# 2_DDR4_16bits.net
KiCad netlist of a schematic drawn in Altium Designer
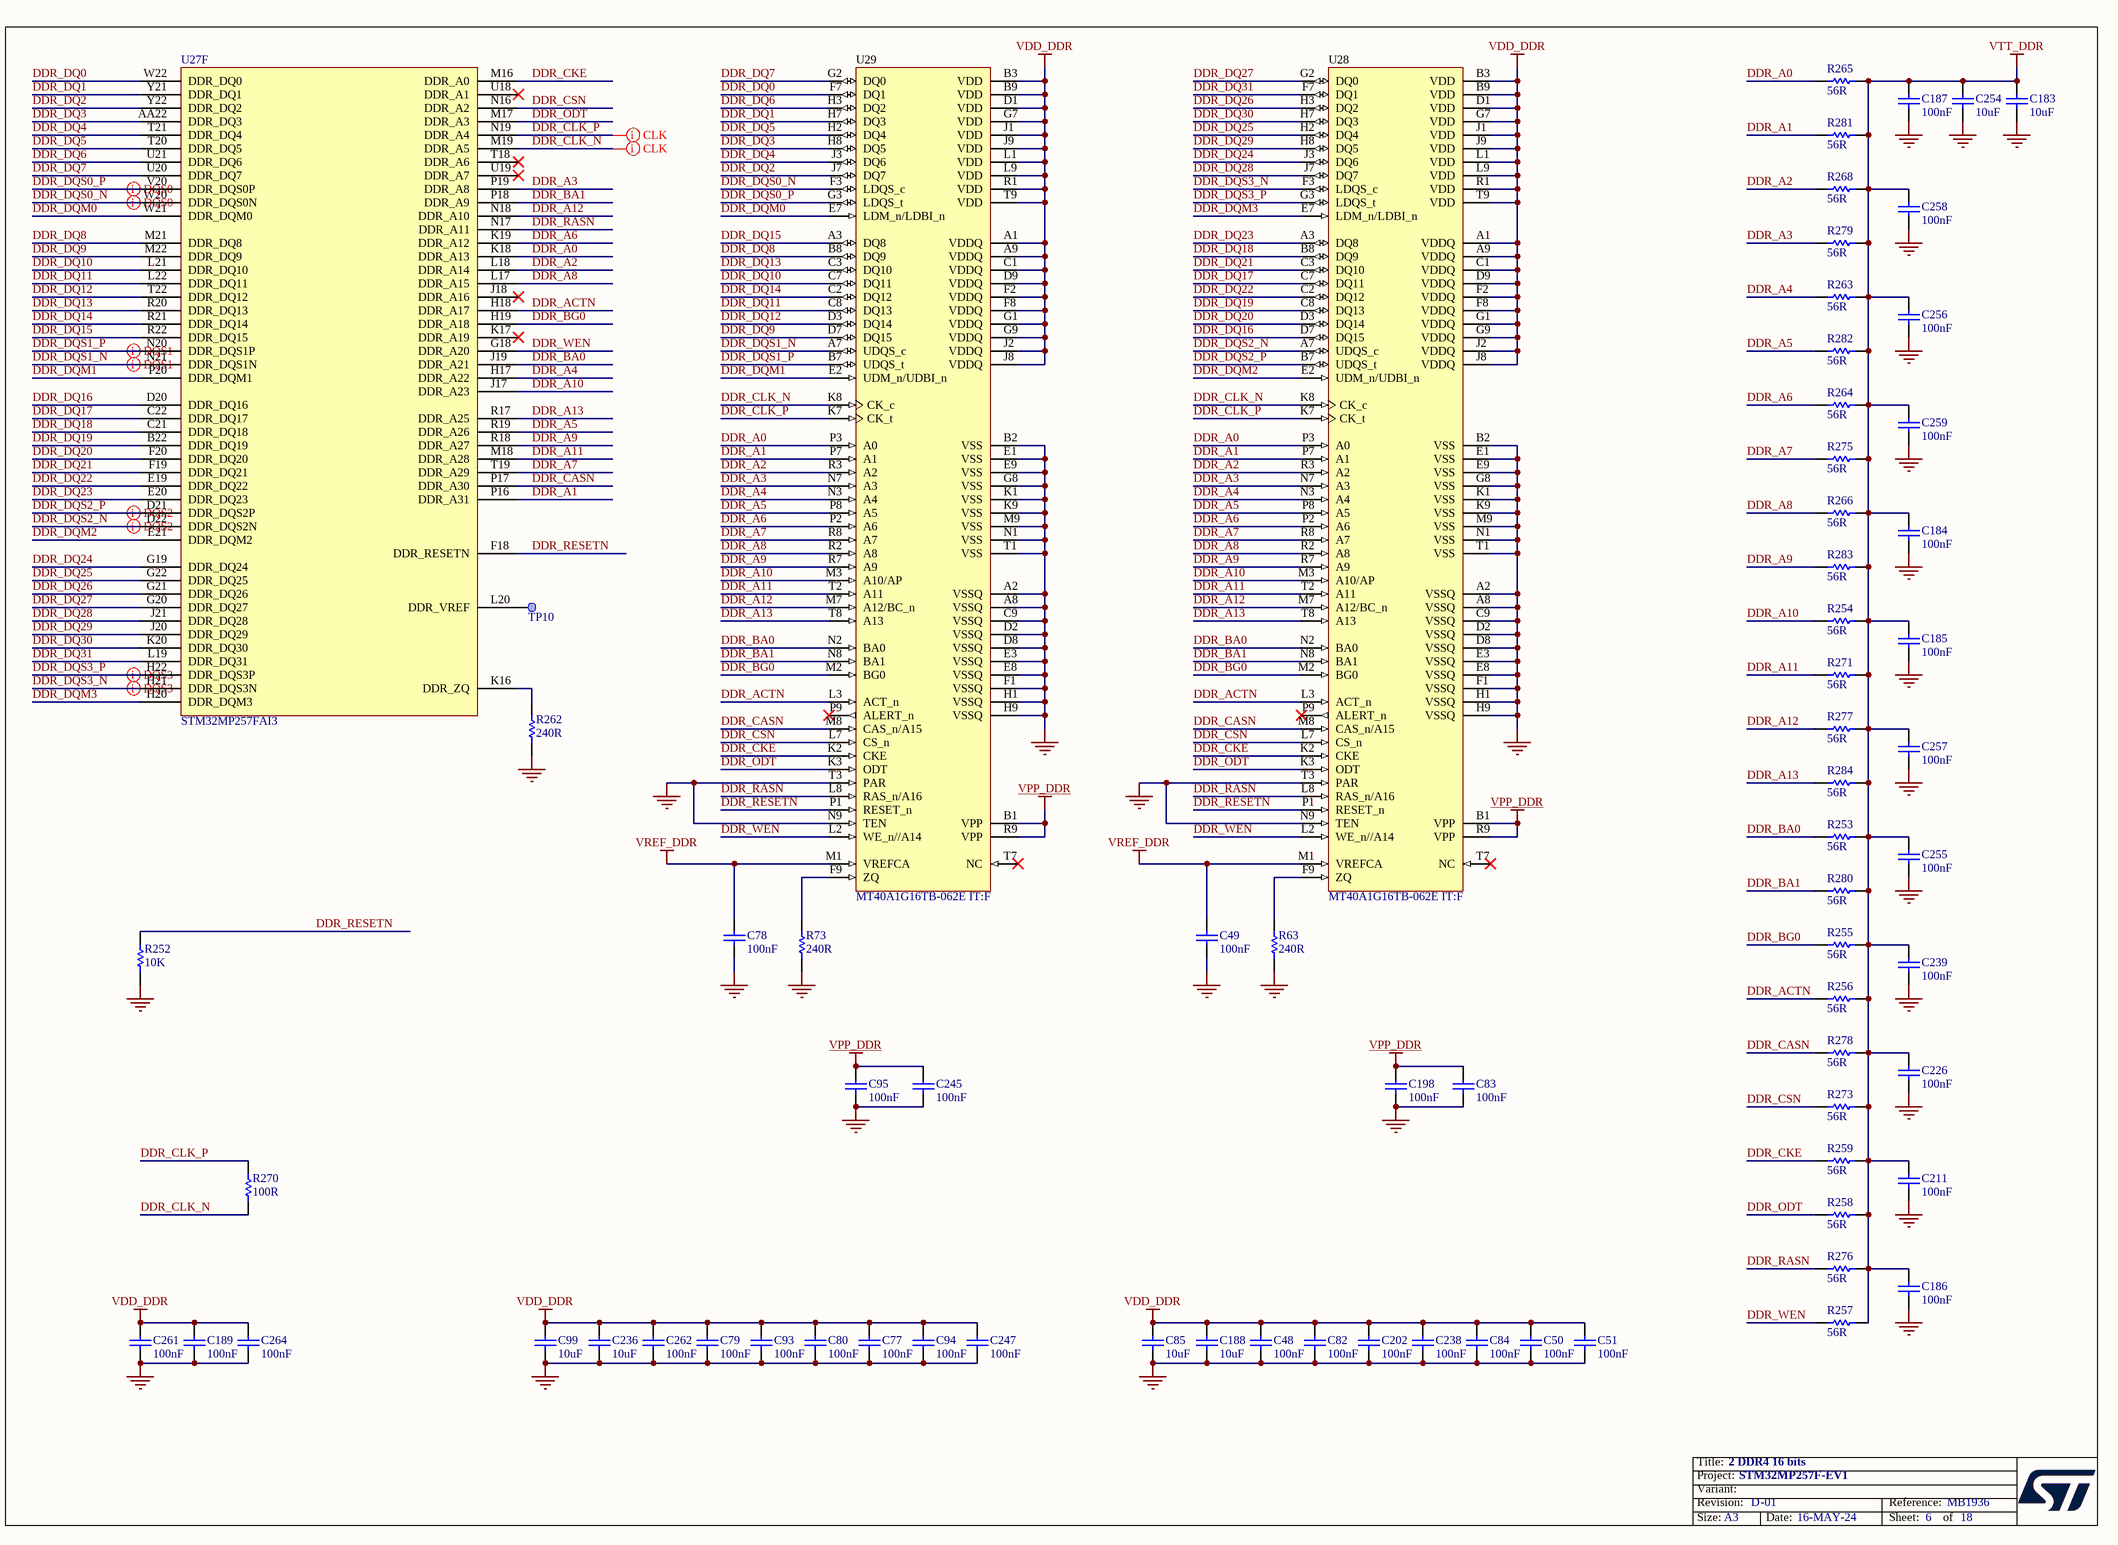
[diagram p0: 2_DDR4_16bits.SchDoc]

(export (version "E")
  (design (tool "Eeschema 10.0.6"))
  (components
    (comp (ref "C48")
      (value "100nF")
      (footprint "MCD_PARTS:C0402")
      (description "Capacitor, MLCC, 100nF, 16V, X7R, +/-10%, 0402, T=0.5mm")
      (fields (field (name "INTERNAL_PART_NUMBER") "MCD-00006") (field (name "MANUFACTURER") "YAGEO"))
      (libsource (lib "MCD_PARTS_database") (part "Capacitor"))
    )
    (comp (ref "C49")
      (value "100nF")
      (footprint "MCD_PARTS:C0402")
      (description "Capacitor, MLCC, 100nF, 16V, X7R, +/-10%, 0402, T=0.5mm")
      (fields (field (name "INTERNAL_PART_NUMBER") "MCD-00006") (field (name "MANUFACTURER") "YAGEO"))
      (libsource (lib "MCD_PARTS_database") (part "Capacitor"))
    )
    (comp (ref "C50")
      (value "100nF")
      (footprint "MCD_PARTS:C0402")
      (description "Capacitor, MLCC, 100nF, 16V, X7R, +/-10%, 0402, T=0.5mm")
      (fields (field (name "INTERNAL_PART_NUMBER") "MCD-00006") (field (name "MANUFACTURER") "YAGEO"))
      (libsource (lib "MCD_PARTS_database") (part "Capacitor"))
    )
    (comp (ref "C51")
      (value "100nF")
      (footprint "MCD_PARTS:C0402")
      (description "Capacitor, MLCC, 100nF, 16V, X7R, +/-10%, 0402, T=0.5mm")
      (fields (field (name "INTERNAL_PART_NUMBER") "MCD-00006") (field (name "MANUFACTURER") "YAGEO"))
      (libsource (lib "MCD_PARTS_database") (part "Capacitor"))
    )
    (comp (ref "C77")
      (value "100nF")
      (footprint "MCD_PARTS:C0402")
      (description "Capacitor, MLCC, 100nF, 16V, X7R, +/-10%, 0402, T=0.5mm")
      (fields (field (name "INTERNAL_PART_NUMBER") "MCD-00006") (field (name "MANUFACTURER") "YAGEO"))
      (libsource (lib "MCD_PARTS_database") (part "Capacitor"))
    )
    (comp (ref "C78")
      (value "100nF")
      (footprint "MCD_PARTS:C0402")
      (description "Capacitor, MLCC, 100nF, 16V, X7R, +/-10%, 0402, T=0.5mm")
      (fields (field (name "INTERNAL_PART_NUMBER") "MCD-00006") (field (name "MANUFACTURER") "YAGEO"))
      (libsource (lib "MCD_PARTS_database") (part "Capacitor"))
    )
    (comp (ref "C79")
      (value "100nF")
      (footprint "MCD_PARTS:C0402")
      (description "Capacitor, MLCC, 100nF, 16V, X7R, +/-10%, 0402, T=0.5mm")
      (fields (field (name "INTERNAL_PART_NUMBER") "MCD-00006") (field (name "MANUFACTURER") "YAGEO"))
      (libsource (lib "MCD_PARTS_database") (part "Capacitor"))
    )
    (comp (ref "C80")
      (value "100nF")
      (footprint "MCD_PARTS:C0402")
      (description "Capacitor, MLCC, 100nF, 16V, X7R, +/-10%, 0402, T=0.5mm")
      (fields (field (name "INTERNAL_PART_NUMBER") "MCD-00006") (field (name "MANUFACTURER") "YAGEO"))
      (libsource (lib "MCD_PARTS_database") (part "Capacitor"))
    )
    (comp (ref "C82")
      (value "100nF")
      (footprint "MCD_PARTS:C0402")
      (description "Capacitor, MLCC, 100nF, 16V, X7R, +/-10%, 0402, T=0.5mm")
      (fields (field (name "INTERNAL_PART_NUMBER") "MCD-00006") (field (name "MANUFACTURER") "YAGEO"))
      (libsource (lib "MCD_PARTS_database") (part "Capacitor"))
    )
    (comp (ref "C83")
      (value "100nF")
      (footprint "MCD_PARTS:C0402")
      (description "Capacitor, MLCC, 100nF, 16V, X7R, +/-10%, 0402, T=0.5mm")
      (fields (field (name "INTERNAL_PART_NUMBER") "MCD-00006") (field (name "MANUFACTURER") "YAGEO"))
      (libsource (lib "MCD_PARTS_database") (part "Capacitor"))
    )
    (comp (ref "C84")
      (value "100nF")
      (footprint "MCD_PARTS:C0402")
      (description "Capacitor, MLCC, 100nF, 16V, X7R, +/-10%, 0402, T=0.5mm")
      (fields (field (name "INTERNAL_PART_NUMBER") "MCD-00006") (field (name "MANUFACTURER") "YAGEO"))
      (libsource (lib "MCD_PARTS_database") (part "Capacitor"))
    )
    (comp (ref "C85")
      (value "10uF")
      (footprint "MCD_PARTS:C0603")
      (description "Capacitor, MLCC, 10uF, 6V3, X5R, +/-20%, 0603, T=0,8mm")
      (fields (field (name "INTERNAL_PART_NUMBER") "MCD-01341") (field (name "MANUFACTURER") "MURATA"))
      (libsource (lib "MCD_PARTS_database") (part "Capacitor"))
    )
    (comp (ref "C93")
      (value "100nF")
      (footprint "MCD_PARTS:C0402")
      (description "Capacitor, MLCC, 100nF, 16V, X7R, +/-10%, 0402, T=0.5mm")
      (fields (field (name "INTERNAL_PART_NUMBER") "MCD-00006") (field (name "MANUFACTURER") "YAGEO"))
      (libsource (lib "MCD_PARTS_database") (part "Capacitor"))
    )
    (comp (ref "C94")
      (value "100nF")
      (footprint "MCD_PARTS:C0402")
      (description "Capacitor, MLCC, 100nF, 16V, X7R, +/-10%, 0402, T=0.5mm")
      (fields (field (name "INTERNAL_PART_NUMBER") "MCD-00006") (field (name "MANUFACTURER") "YAGEO"))
      (libsource (lib "MCD_PARTS_database") (part "Capacitor"))
    )
    (comp (ref "C95")
      (value "100nF")
      (footprint "MCD_PARTS:C0402")
      (description "Capacitor, MLCC, 100nF, 16V, X7R, +/-10%, 0402, T=0.5mm")
      (fields (field (name "INTERNAL_PART_NUMBER") "MCD-00006") (field (name "MANUFACTURER") "YAGEO"))
      (libsource (lib "MCD_PARTS_database") (part "Capacitor"))
    )
    (comp (ref "C99")
      (value "10uF")
      (footprint "MCD_PARTS:C0603")
      (description "Capacitor, MLCC, 10uF, 6V3, X5R, +/-20%, 0603, T=0,8mm")
      (fields (field (name "INTERNAL_PART_NUMBER") "MCD-01341") (field (name "MANUFACTURER") "MURATA"))
      (libsource (lib "MCD_PARTS_database") (part "Capacitor"))
    )
    (comp (ref "C183")
      (value "10uF")
      (footprint "C0603")
      (description "Capacitor, MLCC, 10uF, 10V, X5R, +/-10%, 0603, T=0.8mm")
      (fields (field (name "INTERNAL_PART_NUMBER") "MCD-00099") (field (name "MANUFACTURER") "MURATA"))
      (libsource (lib "MCD_PARTS_database") (part "Capacitor"))
    )
    (comp (ref "C184")
      (value "100nF")
      (footprint "MCD_PARTS:C0402")
      (description "Capacitor, MLCC, 100nF, 16V, X7R, +/-10%, 0402, T=0.5mm")
      (fields (field (name "INTERNAL_PART_NUMBER") "MCD-00006") (field (name "MANUFACTURER") "YAGEO"))
      (libsource (lib "MCD_PARTS_database") (part "Capacitor"))
    )
    (comp (ref "C185")
      (value "100nF")
      (footprint "MCD_PARTS:C0402")
      (description "Capacitor, MLCC, 100nF, 16V, X7R, +/-10%, 0402, T=0.5mm")
      (fields (field (name "INTERNAL_PART_NUMBER") "MCD-00006") (field (name "MANUFACTURER") "YAGEO"))
      (libsource (lib "MCD_PARTS_database") (part "Capacitor"))
    )
    (comp (ref "C186")
      (value "100nF")
      (footprint "MCD_PARTS:C0402")
      (description "Capacitor, MLCC, 100nF, 16V, X7R, +/-10%, 0402, T=0.5mm")
      (fields (field (name "INTERNAL_PART_NUMBER") "MCD-00006") (field (name "MANUFACTURER") "YAGEO"))
      (libsource (lib "MCD_PARTS_database") (part "Capacitor"))
    )
    (comp (ref "C187")
      (value "100nF")
      (footprint "MCD_PARTS:C0402")
      (description "Capacitor, MLCC, 100nF, 16V, X7R, +/-10%, 0402, T=0.5mm")
      (fields (field (name "INTERNAL_PART_NUMBER") "MCD-00006") (field (name "MANUFACTURER") "YAGEO"))
      (libsource (lib "MCD_PARTS_database") (part "Capacitor"))
    )
    (comp (ref "C188")
      (value "10uF")
      (footprint "MCD_PARTS:C0603")
      (description "Capacitor, MLCC, 10uF, 6V3, X5R, +/-20%, 0603, T=0,8mm")
      (fields (field (name "INTERNAL_PART_NUMBER") "MCD-01341") (field (name "MANUFACTURER") "MURATA"))
      (libsource (lib "MCD_PARTS_database") (part "Capacitor"))
    )
    (comp (ref "C189")
      (value "100nF")
      (footprint "MCD_PARTS:C0402")
      (description "Capacitor, MLCC, 100nF, 16V, X7R, +/-10%, 0402, T=0.5mm")
      (fields (field (name "INTERNAL_PART_NUMBER") "MCD-00006") (field (name "MANUFACTURER") "YAGEO"))
      (libsource (lib "MCD_PARTS_database") (part "Capacitor"))
    )
    (comp (ref "C198")
      (value "100nF")
      (footprint "MCD_PARTS:C0402")
      (description "Capacitor, MLCC, 100nF, 16V, X7R, +/-10%, 0402, T=0.5mm")
      (fields (field (name "INTERNAL_PART_NUMBER") "MCD-00006") (field (name "MANUFACTURER") "YAGEO"))
      (libsource (lib "MCD_PARTS_database") (part "Capacitor"))
    )
    (comp (ref "C202")
      (value "100nF")
      (footprint "MCD_PARTS:C0402")
      (description "Capacitor, MLCC, 100nF, 16V, X7R, +/-10%, 0402, T=0.5mm")
      (fields (field (name "INTERNAL_PART_NUMBER") "MCD-00006") (field (name "MANUFACTURER") "YAGEO"))
      (libsource (lib "MCD_PARTS_database") (part "Capacitor"))
    )
    (comp (ref "C211")
      (value "100nF")
      (footprint "MCD_PARTS:C0402")
      (description "Capacitor, MLCC, 100nF, 16V, X7R, +/-10%, 0402, T=0.5mm")
      (fields (field (name "INTERNAL_PART_NUMBER") "MCD-00006") (field (name "MANUFACTURER") "YAGEO"))
      (libsource (lib "MCD_PARTS_database") (part "Capacitor"))
    )
    (comp (ref "C226")
      (value "100nF")
      (footprint "MCD_PARTS:C0402")
      (description "Capacitor, MLCC, 100nF, 16V, X7R, +/-10%, 0402, T=0.5mm")
      (fields (field (name "INTERNAL_PART_NUMBER") "MCD-00006") (field (name "MANUFACTURER") "YAGEO"))
      (libsource (lib "MCD_PARTS_database") (part "Capacitor"))
    )
    (comp (ref "C236")
      (value "10uF")
      (footprint "MCD_PARTS:C0603")
      (description "Capacitor, MLCC, 10uF, 6V3, X5R, +/-20%, 0603, T=0,8mm")
      (fields (field (name "INTERNAL_PART_NUMBER") "MCD-01341") (field (name "MANUFACTURER") "MURATA"))
      (libsource (lib "MCD_PARTS_database") (part "Capacitor"))
    )
    (comp (ref "C238")
      (value "100nF")
      (footprint "MCD_PARTS:C0402")
      (description "Capacitor, MLCC, 100nF, 16V, X7R, +/-10%, 0402, T=0.5mm")
      (fields (field (name "INTERNAL_PART_NUMBER") "MCD-00006") (field (name "MANUFACTURER") "YAGEO"))
      (libsource (lib "MCD_PARTS_database") (part "Capacitor"))
    )
    (comp (ref "C239")
      (value "100nF")
      (footprint "MCD_PARTS:C0402")
      (description "Capacitor, MLCC, 100nF, 16V, X7R, +/-10%, 0402, T=0.5mm")
      (fields (field (name "INTERNAL_PART_NUMBER") "MCD-00006") (field (name "MANUFACTURER") "YAGEO"))
      (libsource (lib "MCD_PARTS_database") (part "Capacitor"))
    )
    (comp (ref "C245")
      (value "100nF")
      (footprint "MCD_PARTS:C0402")
      (description "Capacitor, MLCC, 100nF, 16V, X7R, +/-10%, 0402, T=0.5mm")
      (fields (field (name "INTERNAL_PART_NUMBER") "MCD-00006") (field (name "MANUFACTURER") "YAGEO"))
      (libsource (lib "MCD_PARTS_database") (part "Capacitor"))
    )
    (comp (ref "C247")
      (value "100nF")
      (footprint "MCD_PARTS:C0402")
      (description "Capacitor, MLCC, 100nF, 16V, X7R, +/-10%, 0402, T=0.5mm")
      (fields (field (name "INTERNAL_PART_NUMBER") "MCD-00006") (field (name "MANUFACTURER") "YAGEO"))
      (libsource (lib "MCD_PARTS_database") (part "Capacitor"))
    )
    (comp (ref "C254")
      (value "10uF")
      (footprint "C0603")
      (description "Capacitor, MLCC, 10uF, 10V, X5R, +/-10%, 0603, T=0.8mm")
      (fields (field (name "INTERNAL_PART_NUMBER") "MCD-00099") (field (name "MANUFACTURER") "MURATA"))
      (libsource (lib "MCD_PARTS_database") (part "Capacitor"))
    )
    (comp (ref "C255")
      (value "100nF")
      (footprint "MCD_PARTS:C0402")
      (description "Capacitor, MLCC, 100nF, 16V, X7R, +/-10%, 0402, T=0.5mm")
      (fields (field (name "INTERNAL_PART_NUMBER") "MCD-00006") (field (name "MANUFACTURER") "YAGEO"))
      (libsource (lib "MCD_PARTS_database") (part "Capacitor"))
    )
    (comp (ref "C256")
      (value "100nF")
      (footprint "MCD_PARTS:C0402")
      (description "Capacitor, MLCC, 100nF, 16V, X7R, +/-10%, 0402, T=0.5mm")
      (fields (field (name "INTERNAL_PART_NUMBER") "MCD-00006") (field (name "MANUFACTURER") "YAGEO"))
      (libsource (lib "MCD_PARTS_database") (part "Capacitor"))
    )
    (comp (ref "C257")
      (value "100nF")
      (footprint "MCD_PARTS:C0402")
      (description "Capacitor, MLCC, 100nF, 16V, X7R, +/-10%, 0402, T=0.5mm")
      (fields (field (name "INTERNAL_PART_NUMBER") "MCD-00006") (field (name "MANUFACTURER") "YAGEO"))
      (libsource (lib "MCD_PARTS_database") (part "Capacitor"))
    )
    (comp (ref "C258")
      (value "100nF")
      (footprint "MCD_PARTS:C0402")
      (description "Capacitor, MLCC, 100nF, 16V, X7R, +/-10%, 0402, T=0.5mm")
      (fields (field (name "INTERNAL_PART_NUMBER") "MCD-00006") (field (name "MANUFACTURER") "YAGEO"))
      (libsource (lib "MCD_PARTS_database") (part "Capacitor"))
    )
    (comp (ref "C259")
      (value "100nF")
      (footprint "MCD_PARTS:C0402")
      (description "Capacitor, MLCC, 100nF, 16V, X7R, +/-10%, 0402, T=0.5mm")
      (fields (field (name "INTERNAL_PART_NUMBER") "MCD-00006") (field (name "MANUFACTURER") "YAGEO"))
      (libsource (lib "MCD_PARTS_database") (part "Capacitor"))
    )
    (comp (ref "C261")
      (value "100nF")
      (footprint "MCD_PARTS:C0402")
      (description "Capacitor, MLCC, 100nF, 16V, X7R, +/-10%, 0402, T=0.5mm")
      (fields (field (name "INTERNAL_PART_NUMBER") "MCD-00006") (field (name "MANUFACTURER") "YAGEO"))
      (libsource (lib "MCD_PARTS_database") (part "Capacitor"))
    )
    (comp (ref "C262")
      (value "100nF")
      (footprint "MCD_PARTS:C0402")
      (description "Capacitor, MLCC, 100nF, 16V, X7R, +/-10%, 0402, T=0.5mm")
      (fields (field (name "INTERNAL_PART_NUMBER") "MCD-00006") (field (name "MANUFACTURER") "YAGEO"))
      (libsource (lib "MCD_PARTS_database") (part "Capacitor"))
    )
    (comp (ref "C264")
      (value "100nF")
      (footprint "MCD_PARTS:C0402")
      (description "Capacitor, MLCC, 100nF, 16V, X7R, +/-10%, 0402, T=0.5mm")
      (fields (field (name "INTERNAL_PART_NUMBER") "MCD-00006") (field (name "MANUFACTURER") "YAGEO"))
      (libsource (lib "MCD_PARTS_database") (part "Capacitor"))
    )
    (comp (ref "R63")
      (value "240R")
      (footprint "MCD_PARTS:R0201_H0P23")
      (description "Resistor,240R,0201,1%,1/20W")
      (fields (field (name "INTERNAL_PART_NUMBER") "MCD-02253") (field (name "MANUFACTURER") "YAGEO"))
      (libsource (lib "MCD_PARTS_database") (part "Resistor"))
    )
    (comp (ref "R73")
      (value "240R")
      (footprint "MCD_PARTS:R0201_H0P23")
      (description "Resistor,240R,0201,1%,1/20W")
      (fields (field (name "INTERNAL_PART_NUMBER") "MCD-02253") (field (name "MANUFACTURER") "YAGEO"))
      (libsource (lib "MCD_PARTS_database") (part "Resistor"))
    )
    (comp (ref "R252")
      (value "10K")
      (footprint "MCD_PARTS:R0402")
      (description "Resistor,10K,0402,1%,1/16W")
      (fields (field (name "INTERNAL_PART_NUMBER") "MCD-00053") (field (name "BMS_PART_NUMBER") "9131590"))
      (libsource (lib "MCD_PARTS_database") (part "Resistor"))
    )
    (comp (ref "R253")
      (value "56R")
      (footprint "MCD_PARTS:R0402")
      (description "Resistor, 56R, 0402, +/-1%, 1/16W")
      (fields (field (name "INTERNAL_PART_NUMBER") "MCD-00054") (field (name "MANUFACTURER") "YAGEO"))
      (libsource (lib "MCD_PARTS_database") (part "Resistor"))
    )
    (comp (ref "R254")
      (value "56R")
      (footprint "MCD_PARTS:R0402")
      (description "Resistor, 56R, 0402, +/-1%, 1/16W")
      (fields (field (name "INTERNAL_PART_NUMBER") "MCD-00054") (field (name "MANUFACTURER") "YAGEO"))
      (libsource (lib "MCD_PARTS_database") (part "Resistor"))
    )
    (comp (ref "R255")
      (value "56R")
      (footprint "MCD_PARTS:R0402")
      (description "Resistor, 56R, 0402, +/-1%, 1/16W")
      (fields (field (name "INTERNAL_PART_NUMBER") "MCD-00054") (field (name "MANUFACTURER") "YAGEO"))
      (libsource (lib "MCD_PARTS_database") (part "Resistor"))
    )
    (comp (ref "R256")
      (value "56R")
      (footprint "MCD_PARTS:R0402")
      (description "Resistor, 56R, 0402, +/-1%, 1/16W")
      (fields (field (name "INTERNAL_PART_NUMBER") "MCD-00054") (field (name "MANUFACTURER") "YAGEO"))
      (libsource (lib "MCD_PARTS_database") (part "Resistor"))
    )
    (comp (ref "R257")
      (value "56R")
      (footprint "MCD_PARTS:R0402")
      (description "Resistor, 56R, 0402, +/-1%, 1/16W")
      (fields (field (name "INTERNAL_PART_NUMBER") "MCD-00054") (field (name "MANUFACTURER") "YAGEO"))
      (libsource (lib "MCD_PARTS_database") (part "Resistor"))
    )
    (comp (ref "R258")
      (value "56R")
      (footprint "MCD_PARTS:R0402")
      (description "Resistor, 56R, 0402, +/-1%, 1/16W")
      (fields (field (name "INTERNAL_PART_NUMBER") "MCD-00054") (field (name "MANUFACTURER") "YAGEO"))
      (libsource (lib "MCD_PARTS_database") (part "Resistor"))
    )
    (comp (ref "R259")
      (value "56R")
      (footprint "MCD_PARTS:R0402")
      (description "Resistor, 56R, 0402, +/-1%, 1/16W")
      (fields (field (name "INTERNAL_PART_NUMBER") "MCD-00054") (field (name "MANUFACTURER") "YAGEO"))
      (libsource (lib "MCD_PARTS_database") (part "Resistor"))
    )
    (comp (ref "R262")
      (value "240R")
      (footprint "MCD_PARTS:R0201_H0P23")
      (description "Resistor,240R,0201,1%,1/20W")
      (fields (field (name "INTERNAL_PART_NUMBER") "MCD-02253") (field (name "MANUFACTURER") "YAGEO"))
      (libsource (lib "MCD_PARTS_database") (part "Resistor"))
    )
    (comp (ref "R263")
      (value "56R")
      (footprint "MCD_PARTS:R0402")
      (description "Resistor, 56R, 0402, +/-1%, 1/16W")
      (fields (field (name "INTERNAL_PART_NUMBER") "MCD-00054") (field (name "MANUFACTURER") "YAGEO"))
      (libsource (lib "MCD_PARTS_database") (part "Resistor"))
    )
    (comp (ref "R264")
      (value "56R")
      (footprint "MCD_PARTS:R0402")
      (description "Resistor, 56R, 0402, +/-1%, 1/16W")
      (fields (field (name "INTERNAL_PART_NUMBER") "MCD-00054") (field (name "MANUFACTURER") "YAGEO"))
      (libsource (lib "MCD_PARTS_database") (part "Resistor"))
    )
    (comp (ref "R265")
      (value "56R")
      (footprint "MCD_PARTS:R0402")
      (description "Resistor, 56R, 0402, +/-1%, 1/16W")
      (fields (field (name "INTERNAL_PART_NUMBER") "MCD-00054") (field (name "MANUFACTURER") "YAGEO"))
      (libsource (lib "MCD_PARTS_database") (part "Resistor"))
    )
    (comp (ref "R266")
      (value "56R")
      (footprint "MCD_PARTS:R0402")
      (description "Resistor, 56R, 0402, +/-1%, 1/16W")
      (fields (field (name "INTERNAL_PART_NUMBER") "MCD-00054") (field (name "MANUFACTURER") "YAGEO"))
      (libsource (lib "MCD_PARTS_database") (part "Resistor"))
    )
    (comp (ref "R268")
      (value "56R")
      (footprint "MCD_PARTS:R0402")
      (description "Resistor, 56R, 0402, +/-1%, 1/16W")
      (fields (field (name "INTERNAL_PART_NUMBER") "MCD-00054") (field (name "MANUFACTURER") "YAGEO"))
      (libsource (lib "MCD_PARTS_database") (part "Resistor"))
    )
    (comp (ref "R270")
      (value "100R")
      (footprint "MCD_PARTS:R0402")
      (description "Resistor,100R,0402,0,5%,1/16W,±100ppm/°C")
      (fields (field (name "INTERNAL_PART_NUMBER") "MCD-01819") (field (name "MANUFACTURER") "YAGEO"))
      (libsource (lib "MCD_PARTS_database") (part "Resistor"))
    )
    (comp (ref "R271")
      (value "56R")
      (footprint "MCD_PARTS:R0402")
      (description "Resistor, 56R, 0402, +/-1%, 1/16W")
      (fields (field (name "INTERNAL_PART_NUMBER") "MCD-00054") (field (name "MANUFACTURER") "YAGEO"))
      (libsource (lib "MCD_PARTS_database") (part "Resistor"))
    )
    (comp (ref "R273")
      (value "56R")
      (footprint "MCD_PARTS:R0402")
      (description "Resistor, 56R, 0402, +/-1%, 1/16W")
      (fields (field (name "INTERNAL_PART_NUMBER") "MCD-00054") (field (name "MANUFACTURER") "YAGEO"))
      (libsource (lib "MCD_PARTS_database") (part "Resistor"))
    )
    (comp (ref "R275")
      (value "56R")
      (footprint "MCD_PARTS:R0402")
      (description "Resistor, 56R, 0402, +/-1%, 1/16W")
      (fields (field (name "INTERNAL_PART_NUMBER") "MCD-00054") (field (name "MANUFACTURER") "YAGEO"))
      (libsource (lib "MCD_PARTS_database") (part "Resistor"))
    )
    (comp (ref "R276")
      (value "56R")
      (footprint "MCD_PARTS:R0402")
      (description "Resistor, 56R, 0402, +/-1%, 1/16W")
      (fields (field (name "INTERNAL_PART_NUMBER") "MCD-00054") (field (name "MANUFACTURER") "YAGEO"))
      (libsource (lib "MCD_PARTS_database") (part "Resistor"))
    )
    (comp (ref "R277")
      (value "56R")
      (footprint "MCD_PARTS:R0402")
      (description "Resistor, 56R, 0402, +/-1%, 1/16W")
      (fields (field (name "INTERNAL_PART_NUMBER") "MCD-00054") (field (name "MANUFACTURER") "YAGEO"))
      (libsource (lib "MCD_PARTS_database") (part "Resistor"))
    )
    (comp (ref "R278")
      (value "56R")
      (footprint "MCD_PARTS:R0402")
      (description "Resistor, 56R, 0402, +/-1%, 1/16W")
      (fields (field (name "INTERNAL_PART_NUMBER") "MCD-00054") (field (name "MANUFACTURER") "YAGEO"))
      (libsource (lib "MCD_PARTS_database") (part "Resistor"))
    )
    (comp (ref "R279")
      (value "56R")
      (footprint "MCD_PARTS:R0402")
      (description "Resistor, 56R, 0402, +/-1%, 1/16W")
      (fields (field (name "INTERNAL_PART_NUMBER") "MCD-00054") (field (name "MANUFACTURER") "YAGEO"))
      (libsource (lib "MCD_PARTS_database") (part "Resistor"))
    )
    (comp (ref "R280")
      (value "56R")
      (footprint "MCD_PARTS:R0402")
      (description "Resistor, 56R, 0402, +/-1%, 1/16W")
      (fields (field (name "INTERNAL_PART_NUMBER") "MCD-00054") (field (name "MANUFACTURER") "YAGEO"))
      (libsource (lib "MCD_PARTS_database") (part "Resistor"))
    )
    (comp (ref "R281")
      (value "56R")
      (footprint "MCD_PARTS:R0402")
      (description "Resistor, 56R, 0402, +/-1%, 1/16W")
      (fields (field (name "INTERNAL_PART_NUMBER") "MCD-00054") (field (name "MANUFACTURER") "YAGEO"))
      (libsource (lib "MCD_PARTS_database") (part "Resistor"))
    )
    (comp (ref "R282")
      (value "56R")
      (footprint "MCD_PARTS:R0402")
      (description "Resistor, 56R, 0402, +/-1%, 1/16W")
      (fields (field (name "INTERNAL_PART_NUMBER") "MCD-00054") (field (name "MANUFACTURER") "YAGEO"))
      (libsource (lib "MCD_PARTS_database") (part "Resistor"))
    )
    (comp (ref "R283")
      (value "56R")
      (footprint "MCD_PARTS:R0402")
      (description "Resistor, 56R, 0402, +/-1%, 1/16W")
      (fields (field (name "INTERNAL_PART_NUMBER") "MCD-00054") (field (name "MANUFACTURER") "YAGEO"))
      (libsource (lib "MCD_PARTS_database") (part "Resistor"))
    )
    (comp (ref "R284")
      (value "56R")
      (footprint "MCD_PARTS:R0402")
      (description "Resistor, 56R, 0402, +/-1%, 1/16W")
      (fields (field (name "INTERNAL_PART_NUMBER") "MCD-00054") (field (name "MANUFACTURER") "YAGEO"))
      (libsource (lib "MCD_PARTS_database") (part "Resistor"))
    )
    (comp (ref "TP10")
      (value "Test Point")
      (footprint "MCD_PARTS:TP_SMD_0-6MM")
      (description "Test Point 0.6mm")
      (fields (field (name "INTERNAL_PART_NUMBER") "MCD-00631"))
      (libsource (lib "MCD_PARTS_database") (part "Test Point"))
    )
    (comp (ref "U27")
      (value "STM32MP257FAI3")
      (footprint "ICC_LFBGA436_18X18_P080_H1P70_STM32MP257_CODE-B0D1")
      (description "MPU, ARM Cortex-A35 + M33 32-bit MPU, 808KB RAM, With Crypto")
      (fields
        (field (name "INTERNAL_PART_NUMBER") "MCD-02000")
        (field (name "MANUFACTURER") "STMICROELECTRONICS")
      )
      (libsource (lib "MCD_PARTS_database") (part "STM32MP257FAI3"))
    )
    (comp (ref "U28")
      (value "MT40A1G16TB-062E IT:F")
      (footprint "MCD_PARTS:ICC_FBGA96_TB_7P5X13_P080")
      (description "Memory, DDR4 SDRAM, 1V2, 16Gbit, FBGA96")
      (fields (field (name "INTERNAL_PART_NUMBER") "MCD-03523") (field (name "MANUFACTURER") "MICRON"))
      (libsource (lib "MCD_PARTS_database") (part "MT40A1G16TB-062E IT{colon}F"))
    )
    (comp (ref "U29")
      (value "MT40A1G16TB-062E IT:F")
      (footprint "MCD_PARTS:ICC_FBGA96_TB_7P5X13_P080")
      (description "Memory, DDR4 SDRAM, 1V2, 16Gbit, FBGA96")
      (fields (field (name "INTERNAL_PART_NUMBER") "MCD-03523") (field (name "MANUFACTURER") "MICRON"))
      (libsource (lib "MCD_PARTS_database") (part "MT40A1G16TB-062E IT{colon}F"))
    )
  )
  (nets
    (net (code "1") (name "/DDR_A0") (class "Default")
      (node (ref "R265") (pin "1") (pinfunction "1_1") (pintype "passive"))
      (node (ref "U27") (pin "K18") (pinfunction "DDR_A13_K18") (pintype "passive"))
      (node (ref "U28") (pin "P3") (pinfunction "A0_P3") (pintype "input"))
      (node (ref "U29") (pin "P3") (pinfunction "A0_P3") (pintype "input"))
    )
    (net (code "2") (name "/DDR_A1") (class "Default")
      (node (ref "R281") (pin "1") (pinfunction "1_1") (pintype "passive"))
      (node (ref "U27") (pin "P16") (pinfunction "DDR_A31_P16") (pintype "passive"))
      (node (ref "U28") (pin "P7") (pinfunction "A1_P7") (pintype "input"))
      (node (ref "U29") (pin "P7") (pinfunction "A1_P7") (pintype "input"))
    )
    (net (code "3") (name "/DDR_A2") (class "Default")
      (node (ref "R268") (pin "1") (pinfunction "1_1") (pintype "passive"))
      (node (ref "U27") (pin "L18") (pinfunction "DDR_A14_L18") (pintype "passive"))
      (node (ref "U28") (pin "R3") (pinfunction "A2_R3") (pintype "input"))
      (node (ref "U29") (pin "R3") (pinfunction "A2_R3") (pintype "input"))
    )
    (net (code "4") (name "/DDR_A3") (class "Default")
      (node (ref "R279") (pin "1") (pinfunction "1_1") (pintype "passive"))
      (node (ref "U27") (pin "P19") (pinfunction "DDR_A8_P19") (pintype "passive"))
      (node (ref "U28") (pin "N7") (pinfunction "A3_N7") (pintype "input"))
      (node (ref "U29") (pin "N7") (pinfunction "A3_N7") (pintype "input"))
    )
    (net (code "5") (name "/DDR_A4") (class "Default")
      (node (ref "R263") (pin "1") (pinfunction "1_1") (pintype "passive"))
      (node (ref "U27") (pin "H17") (pinfunction "DDR_A22_H17") (pintype "passive"))
      (node (ref "U28") (pin "N3") (pinfunction "A4_N3") (pintype "input"))
      (node (ref "U29") (pin "N3") (pinfunction "A4_N3") (pintype "input"))
    )
    (net (code "6") (name "/DDR_A5") (class "Default")
      (node (ref "R282") (pin "1") (pinfunction "1_1") (pintype "passive"))
      (node (ref "U27") (pin "R19") (pinfunction "DDR_A26_R19") (pintype "passive"))
      (node (ref "U28") (pin "P8") (pinfunction "A5_P8") (pintype "input"))
      (node (ref "U29") (pin "P8") (pinfunction "A5_P8") (pintype "input"))
    )
    (net (code "7") (name "/DDR_A6") (class "Default")
      (node (ref "R264") (pin "1") (pinfunction "1_1") (pintype "passive"))
      (node (ref "U27") (pin "K19") (pinfunction "DDR_A12_K19") (pintype "passive"))
      (node (ref "U28") (pin "P2") (pinfunction "A6_P2") (pintype "input"))
      (node (ref "U29") (pin "P2") (pinfunction "A6_P2") (pintype "input"))
    )
    (net (code "8") (name "/DDR_A7") (class "Default")
      (node (ref "R275") (pin "1") (pinfunction "1_1") (pintype "passive"))
      (node (ref "U27") (pin "T19") (pinfunction "DDR_A29_T19") (pintype "passive"))
      (node (ref "U28") (pin "R8") (pinfunction "A7_R8") (pintype "input"))
      (node (ref "U29") (pin "R8") (pinfunction "A7_R8") (pintype "input"))
    )
    (net (code "9") (name "/DDR_A8") (class "Default")
      (node (ref "R266") (pin "1") (pinfunction "1_1") (pintype "passive"))
      (node (ref "U27") (pin "L17") (pinfunction "DDR_A15_L17") (pintype "passive"))
      (node (ref "U28") (pin "R2") (pinfunction "A8_R2") (pintype "input"))
      (node (ref "U29") (pin "R2") (pinfunction "A8_R2") (pintype "input"))
    )
    (net (code "10") (name "/DDR_A9") (class "Default")
      (node (ref "R283") (pin "1") (pinfunction "1_1") (pintype "passive"))
      (node (ref "U27") (pin "R18") (pinfunction "DDR_A27_R18") (pintype "passive"))
      (node (ref "U28") (pin "R7") (pinfunction "A9_R7") (pintype "input"))
      (node (ref "U29") (pin "R7") (pinfunction "A9_R7") (pintype "input"))
    )
    (net (code "11") (name "/DDR_A10") (class "Default")
      (node (ref "R254") (pin "1") (pinfunction "1_1") (pintype "passive"))
      (node (ref "U27") (pin "J17") (pinfunction "DDR_A23_J17") (pintype "passive"))
      (node (ref "U28") (pin "M3") (pinfunction "A10/AP_M3") (pintype "input"))
      (node (ref "U29") (pin "M3") (pinfunction "A10/AP_M3") (pintype "input"))
    )
    (net (code "12") (name "/DDR_A11") (class "Default")
      (node (ref "R271") (pin "1") (pinfunction "1_1") (pintype "passive"))
      (node (ref "U27") (pin "M18") (pinfunction "DDR_A28_M18") (pintype "passive"))
      (node (ref "U28") (pin "T2") (pinfunction "A11_T2") (pintype "input"))
      (node (ref "U29") (pin "T2") (pinfunction "A11_T2") (pintype "input"))
    )
    (net (code "13") (name "/DDR_A12") (class "Default")
      (node (ref "R277") (pin "1") (pinfunction "1_1") (pintype "passive"))
      (node (ref "U27") (pin "N18") (pinfunction "DDR_A10_N18") (pintype "passive"))
      (node (ref "U28") (pin "M7") (pinfunction "A12/BC_n_M7") (pintype "input"))
      (node (ref "U29") (pin "M7") (pinfunction "A12/BC_n_M7") (pintype "input"))
    )
    (net (code "14") (name "/DDR_A13") (class "Default")
      (node (ref "R284") (pin "1") (pinfunction "1_1") (pintype "passive"))
      (node (ref "U27") (pin "R17") (pinfunction "DDR_A25_R17") (pintype "passive"))
      (node (ref "U28") (pin "T8") (pinfunction "A13_T8") (pintype "input"))
      (node (ref "U29") (pin "T8") (pinfunction "A13_T8") (pintype "input"))
    )
    (net (code "15") (name "/DDR_ACTN") (class "Default")
      (node (ref "R256") (pin "1") (pinfunction "1_1") (pintype "passive"))
      (node (ref "U27") (pin "H18") (pinfunction "DDR_A17_H18") (pintype "passive"))
      (node (ref "U28") (pin "L3") (pinfunction "ACT_n_L3") (pintype "input"))
      (node (ref "U29") (pin "L3") (pinfunction "ACT_n_L3") (pintype "input"))
    )
    (net (code "16") (name "/DDR_BA0") (class "Default")
      (node (ref "R253") (pin "1") (pinfunction "1_1") (pintype "passive"))
      (node (ref "U27") (pin "J19") (pinfunction "DDR_A21_J19") (pintype "passive"))
      (node (ref "U28") (pin "N2") (pinfunction "BA0_N2") (pintype "input"))
      (node (ref "U29") (pin "N2") (pinfunction "BA0_N2") (pintype "input"))
    )
    (net (code "17") (name "/DDR_BA1") (class "Default")
      (node (ref "R280") (pin "1") (pinfunction "1_1") (pintype "passive"))
      (node (ref "U27") (pin "P18") (pinfunction "DDR_A9_P18") (pintype "passive"))
      (node (ref "U28") (pin "N8") (pinfunction "BA1_N8") (pintype "input"))
      (node (ref "U29") (pin "N8") (pinfunction "BA1_N8") (pintype "input"))
    )
    (net (code "18") (name "/DDR_BG0") (class "Default")
      (node (ref "R255") (pin "1") (pinfunction "1_1") (pintype "passive"))
      (node (ref "U27") (pin "H19") (pinfunction "DDR_A18_H19") (pintype "passive"))
      (node (ref "U28") (pin "M2") (pinfunction "BG0_M2") (pintype "input"))
      (node (ref "U29") (pin "M2") (pinfunction "BG0_M2") (pintype "input"))
    )
    (net (code "19") (name "/DDR_CASN") (class "Default")
      (node (ref "R278") (pin "1") (pinfunction "1_1") (pintype "passive"))
      (node (ref "U27") (pin "P17") (pinfunction "DDR_A30_P17") (pintype "passive"))
      (node (ref "U28") (pin "M8") (pinfunction "CAS_n/A15_M8") (pintype "input"))
      (node (ref "U29") (pin "M8") (pinfunction "CAS_n/A15_M8") (pintype "input"))
    )
    (net (code "20") (name "/DDR_CKE") (class "Default")
      (node (ref "R259") (pin "1") (pinfunction "1_1") (pintype "passive"))
      (node (ref "U27") (pin "M16") (pinfunction "DDR_A0_M16") (pintype "passive"))
      (node (ref "U28") (pin "K2") (pinfunction "CKE_K2") (pintype "input"))
      (node (ref "U29") (pin "K2") (pinfunction "CKE_K2") (pintype "input"))
    )
    (net (code "21") (name "/DDR_CLK_N") (class "Default")
      (node (ref "R270") (pin "2") (pinfunction "2_2") (pintype "passive"))
      (node (ref "U27") (pin "M19") (pinfunction "DDR_A5_M19") (pintype "passive"))
      (node (ref "U28") (pin "K8") (pinfunction "CK_c_K8") (pintype "input"))
      (node (ref "U29") (pin "K8") (pinfunction "CK_c_K8") (pintype "input"))
    )
    (net (code "22") (name "/DDR_CLK_P") (class "Default")
      (node (ref "R270") (pin "1") (pinfunction "1_1") (pintype "passive"))
      (node (ref "U27") (pin "N19") (pinfunction "DDR_A4_N19") (pintype "passive"))
      (node (ref "U28") (pin "K7") (pinfunction "CK_t_K7") (pintype "input"))
      (node (ref "U29") (pin "K7") (pinfunction "CK_t_K7") (pintype "input"))
    )
    (net (code "23") (name "/DDR_CSN") (class "Default")
      (node (ref "R273") (pin "1") (pinfunction "1_1") (pintype "passive"))
      (node (ref "U27") (pin "N16") (pinfunction "DDR_A2_N16") (pintype "passive"))
      (node (ref "U28") (pin "L7") (pinfunction "CS_n_L7") (pintype "input"))
      (node (ref "U29") (pin "L7") (pinfunction "CS_n_L7") (pintype "input"))
    )
    (net (code "24") (name "/DDR_DQ0") (class "Default")
      (node (ref "U27") (pin "W22") (pinfunction "DDR_DQ0_W22") (pintype "passive"))
      (node (ref "U29") (pin "F7") (pinfunction "DQ1_F7") (pintype "bidirectional"))
    )
    (net (code "25") (name "/DDR_DQ1") (class "Default")
      (node (ref "U27") (pin "Y21") (pinfunction "DDR_DQ1_Y21") (pintype "passive"))
      (node (ref "U29") (pin "H7") (pinfunction "DQ3_H7") (pintype "bidirectional"))
    )
    (net (code "26") (name "/DDR_DQ2") (class "Default")
      (node (ref "U27") (pin "Y22") (pinfunction "DDR_DQ2_Y22") (pintype "passive"))
      (node (ref "U29") (pin "J7") (pinfunction "DQ7_J7") (pintype "bidirectional"))
    )
    (net (code "27") (name "/DDR_DQ3") (class "Default")
      (node (ref "U27") (pin "AA22") (pinfunction "DDR_DQ3_AA22") (pintype "passive"))
      (node (ref "U29") (pin "H8") (pinfunction "DQ5_H8") (pintype "bidirectional"))
    )
    (net (code "28") (name "/DDR_DQ4") (class "Default")
      (node (ref "U27") (pin "T21") (pinfunction "DDR_DQ4_T21") (pintype "passive"))
      (node (ref "U29") (pin "J3") (pinfunction "DQ6_J3") (pintype "bidirectional"))
    )
    (net (code "29") (name "/DDR_DQ5") (class "Default")
      (node (ref "U27") (pin "T20") (pinfunction "DDR_DQ5_T20") (pintype "passive"))
      (node (ref "U29") (pin "H2") (pinfunction "DQ4_H2") (pintype "bidirectional"))
    )
    (net (code "30") (name "/DDR_DQ6") (class "Default")
      (node (ref "U27") (pin "U21") (pinfunction "DDR_DQ6_U21") (pintype "passive"))
      (node (ref "U29") (pin "H3") (pinfunction "DQ2_H3") (pintype "bidirectional"))
    )
    (net (code "31") (name "/DDR_DQ7") (class "Default")
      (node (ref "U27") (pin "U20") (pinfunction "DDR_DQ7_U20") (pintype "passive"))
      (node (ref "U29") (pin "G2") (pinfunction "DQ0_G2") (pintype "bidirectional"))
    )
    (net (code "32") (name "/DDR_DQ8") (class "Default")
      (node (ref "U27") (pin "M21") (pinfunction "DDR_DQ8_M21") (pintype "passive"))
      (node (ref "U29") (pin "B8") (pinfunction "DQ9_B8") (pintype "bidirectional"))
    )
    (net (code "33") (name "/DDR_DQ9") (class "Default")
      (node (ref "U27") (pin "M22") (pinfunction "DDR_DQ9_M22") (pintype "passive"))
      (node (ref "U29") (pin "D7") (pinfunction "DQ15_D7") (pintype "bidirectional"))
    )
    (net (code "34") (name "/DDR_DQ10") (class "Default")
      (node (ref "U27") (pin "L21") (pinfunction "DDR_DQ10_L21") (pintype "passive"))
      (node (ref "U29") (pin "C7") (pinfunction "DQ11_C7") (pintype "bidirectional"))
    )
    (net (code "35") (name "/DDR_DQ11") (class "Default")
      (node (ref "U27") (pin "L22") (pinfunction "DDR_DQ11_L22") (pintype "passive"))
      (node (ref "U29") (pin "C8") (pinfunction "DQ13_C8") (pintype "bidirectional"))
    )
    (net (code "36") (name "/DDR_DQ12") (class "Default")
      (node (ref "U27") (pin "T22") (pinfunction "DDR_DQ12_T22") (pintype "passive"))
      (node (ref "U29") (pin "D3") (pinfunction "DQ14_D3") (pintype "bidirectional"))
    )
    (net (code "37") (name "/DDR_DQ13") (class "Default")
      (node (ref "U27") (pin "R20") (pinfunction "DDR_DQ13_R20") (pintype "passive"))
      (node (ref "U29") (pin "C3") (pinfunction "DQ10_C3") (pintype "bidirectional"))
    )
    (net (code "38") (name "/DDR_DQ14") (class "Default")
      (node (ref "U27") (pin "R21") (pinfunction "DDR_DQ14_R21") (pintype "passive"))
      (node (ref "U29") (pin "C2") (pinfunction "DQ12_C2") (pintype "bidirectional"))
    )
    (net (code "39") (name "/DDR_DQ15") (class "Default")
      (node (ref "U27") (pin "R22") (pinfunction "DDR_DQ15_R22") (pintype "passive"))
      (node (ref "U29") (pin "A3") (pinfunction "DQ8_A3") (pintype "bidirectional"))
    )
    (net (code "40") (name "/DDR_DQ16") (class "Default")
      (node (ref "U27") (pin "D20") (pinfunction "DDR_DQ16_D20") (pintype "passive"))
      (node (ref "U28") (pin "D7") (pinfunction "DQ15_D7") (pintype "bidirectional"))
    )
    (net (code "41") (name "/DDR_DQ17") (class "Default")
      (node (ref "U27") (pin "C22") (pinfunction "DDR_DQ17_C22") (pintype "passive"))
      (node (ref "U28") (pin "C7") (pinfunction "DQ11_C7") (pintype "bidirectional"))
    )
    (net (code "42") (name "/DDR_DQ18") (class "Default")
      (node (ref "U27") (pin "C21") (pinfunction "DDR_DQ18_C21") (pintype "passive"))
      (node (ref "U28") (pin "B8") (pinfunction "DQ9_B8") (pintype "bidirectional"))
    )
    (net (code "43") (name "/DDR_DQ19") (class "Default")
      (node (ref "U27") (pin "B22") (pinfunction "DDR_DQ19_B22") (pintype "passive"))
      (node (ref "U28") (pin "C8") (pinfunction "DQ13_C8") (pintype "bidirectional"))
    )
    (net (code "44") (name "/DDR_DQ20") (class "Default")
      (node (ref "U27") (pin "F20") (pinfunction "DDR_DQ20_F20") (pintype "passive"))
      (node (ref "U28") (pin "D3") (pinfunction "DQ14_D3") (pintype "bidirectional"))
    )
    (net (code "45") (name "/DDR_DQ21") (class "Default")
      (node (ref "U27") (pin "F19") (pinfunction "DDR_DQ21_F19") (pintype "passive"))
      (node (ref "U28") (pin "C3") (pinfunction "DQ10_C3") (pintype "bidirectional"))
    )
    (net (code "46") (name "/DDR_DQ22") (class "Default")
      (node (ref "U27") (pin "E19") (pinfunction "DDR_DQ22_E19") (pintype "passive"))
      (node (ref "U28") (pin "C2") (pinfunction "DQ12_C2") (pintype "bidirectional"))
    )
    (net (code "47") (name "/DDR_DQ23") (class "Default")
      (node (ref "U27") (pin "E20") (pinfunction "DDR_DQ23_E20") (pintype "passive"))
      (node (ref "U28") (pin "A3") (pinfunction "DQ8_A3") (pintype "bidirectional"))
    )
    (net (code "48") (name "/DDR_DQ24") (class "Default")
      (node (ref "U27") (pin "G19") (pinfunction "DDR_DQ24_G19") (pintype "passive"))
      (node (ref "U28") (pin "J3") (pinfunction "DQ6_J3") (pintype "bidirectional"))
    )
    (net (code "49") (name "/DDR_DQ25") (class "Default")
      (node (ref "U27") (pin "G22") (pinfunction "DDR_DQ25_G22") (pintype "passive"))
      (node (ref "U28") (pin "H2") (pinfunction "DQ4_H2") (pintype "bidirectional"))
    )
    (net (code "50") (name "/DDR_DQ26") (class "Default")
      (node (ref "U27") (pin "G21") (pinfunction "DDR_DQ26_G21") (pintype "passive"))
      (node (ref "U28") (pin "H3") (pinfunction "DQ2_H3") (pintype "bidirectional"))
    )
    (net (code "51") (name "/DDR_DQ27") (class "Default")
      (node (ref "U27") (pin "G20") (pinfunction "DDR_DQ27_G20") (pintype "passive"))
      (node (ref "U28") (pin "G2") (pinfunction "DQ0_G2") (pintype "bidirectional"))
    )
    (net (code "52") (name "/DDR_DQ28") (class "Default")
      (node (ref "U27") (pin "J21") (pinfunction "DDR_DQ28_J21") (pintype "passive"))
      (node (ref "U28") (pin "J7") (pinfunction "DQ7_J7") (pintype "bidirectional"))
    )
    (net (code "53") (name "/DDR_DQ29") (class "Default")
      (node (ref "U27") (pin "J20") (pinfunction "DDR_DQ29_J20") (pintype "passive"))
      (node (ref "U28") (pin "H8") (pinfunction "DQ5_H8") (pintype "bidirectional"))
    )
    (net (code "54") (name "/DDR_DQ30") (class "Default")
      (node (ref "U27") (pin "K20") (pinfunction "DDR_DQ30_K20") (pintype "passive"))
      (node (ref "U28") (pin "H7") (pinfunction "DQ3_H7") (pintype "bidirectional"))
    )
    (net (code "55") (name "/DDR_DQ31") (class "Default")
      (node (ref "U27") (pin "L19") (pinfunction "DDR_DQ31_L19") (pintype "passive"))
      (node (ref "U28") (pin "F7") (pinfunction "DQ1_F7") (pintype "bidirectional"))
    )
    (net (code "56") (name "/DDR_DQM0") (class "Default")
      (node (ref "U27") (pin "W21") (pinfunction "DDR_DQM0_W21") (pintype "passive"))
      (node (ref "U29") (pin "E7") (pinfunction "LDM_n/LDBI_n_E7") (pintype "input"))
    )
    (net (code "57") (name "/DDR_DQM1") (class "Default")
      (node (ref "U27") (pin "P20") (pinfunction "DDR_DQM1_P20") (pintype "passive"))
      (node (ref "U29") (pin "E2") (pinfunction "UDM_n/UDBI_n_E2") (pintype "input"))
    )
    (net (code "58") (name "/DDR_DQM2") (class "Default")
      (node (ref "U27") (pin "E21") (pinfunction "DDR_DQM2_E21") (pintype "passive"))
      (node (ref "U28") (pin "E2") (pinfunction "UDM_n/UDBI_n_E2") (pintype "input"))
    )
    (net (code "59") (name "/DDR_DQM3") (class "Default")
      (node (ref "U27") (pin "H20") (pinfunction "DDR_DQM3_H20") (pintype "passive"))
      (node (ref "U28") (pin "E7") (pinfunction "LDM_n/LDBI_n_E7") (pintype "input"))
    )
    (net (code "60") (name "/DDR_DQS0_N") (class "Default")
      (node (ref "U27") (pin "W20") (pinfunction "DDR_DQS0N_W20") (pintype "passive"))
      (node (ref "U29") (pin "F3") (pinfunction "LDQS_c_F3") (pintype "bidirectional"))
    )
    (net (code "61") (name "/DDR_DQS0_P") (class "Default")
      (node (ref "U27") (pin "V20") (pinfunction "DDR_DQS0P_V20") (pintype "passive"))
      (node (ref "U29") (pin "G3") (pinfunction "LDQS_t_G3") (pintype "bidirectional"))
    )
    (net (code "62") (name "/DDR_DQS1_N") (class "Default")
      (node (ref "U27") (pin "N21") (pinfunction "DDR_DQS1N_N21") (pintype "passive"))
      (node (ref "U29") (pin "A7") (pinfunction "UDQS_c_A7") (pintype "bidirectional"))
    )
    (net (code "63") (name "/DDR_DQS1_P") (class "Default")
      (node (ref "U27") (pin "N20") (pinfunction "DDR_DQS1P_N20") (pintype "passive"))
      (node (ref "U29") (pin "B7") (pinfunction "UDQS_t_B7") (pintype "bidirectional"))
    )
    (net (code "64") (name "/DDR_DQS2_N") (class "Default")
      (node (ref "U27") (pin "D22") (pinfunction "DDR_DQS2N_D22") (pintype "passive"))
      (node (ref "U28") (pin "A7") (pinfunction "UDQS_c_A7") (pintype "bidirectional"))
    )
    (net (code "65") (name "/DDR_DQS2_P") (class "Default")
      (node (ref "U27") (pin "D21") (pinfunction "DDR_DQS2P_D21") (pintype "passive"))
      (node (ref "U28") (pin "B7") (pinfunction "UDQS_t_B7") (pintype "bidirectional"))
    )
    (net (code "66") (name "/DDR_DQS3_N") (class "Default")
      (node (ref "U27") (pin "H21") (pinfunction "DDR_DQS3N_H21") (pintype "passive"))
      (node (ref "U28") (pin "F3") (pinfunction "LDQS_c_F3") (pintype "bidirectional"))
    )
    (net (code "67") (name "/DDR_DQS3_P") (class "Default")
      (node (ref "U27") (pin "H22") (pinfunction "DDR_DQS3P_H22") (pintype "passive"))
      (node (ref "U28") (pin "G3") (pinfunction "LDQS_t_G3") (pintype "bidirectional"))
    )
    (net (code "68") (name "/DDR_ODT") (class "Default")
      (node (ref "R258") (pin "1") (pinfunction "1_1") (pintype "passive"))
      (node (ref "U27") (pin "M17") (pinfunction "DDR_A3_M17") (pintype "passive"))
      (node (ref "U28") (pin "K3") (pinfunction "ODT_K3") (pintype "input"))
      (node (ref "U29") (pin "K3") (pinfunction "ODT_K3") (pintype "input"))
    )
    (net (code "69") (name "/DDR_RASN") (class "Default")
      (node (ref "R276") (pin "1") (pinfunction "1_1") (pintype "passive"))
      (node (ref "U27") (pin "N17") (pinfunction "DDR_A11_N17") (pintype "passive"))
      (node (ref "U28") (pin "L8") (pinfunction "RAS_n/A16_L8") (pintype "input"))
      (node (ref "U29") (pin "L8") (pinfunction "RAS_n/A16_L8") (pintype "input"))
    )
    (net (code "70") (name "/DDR_RESETN") (class "Default")
      (node (ref "R252") (pin "2") (pinfunction "2_2") (pintype "passive"))
      (node (ref "U27") (pin "F18") (pinfunction "DDR_RESETN_F18") (pintype "passive"))
      (node (ref "U28") (pin "P1") (pinfunction "RESET_n_P1") (pintype "input"))
      (node (ref "U29") (pin "P1") (pinfunction "RESET_n_P1") (pintype "input"))
    )
    (net (code "71") (name "/DDR_WEN") (class "Default")
      (node (ref "R257") (pin "1") (pinfunction "1_1") (pintype "passive"))
      (node (ref "U27") (pin "G18") (pinfunction "DDR_A20_G18") (pintype "passive"))
      (node (ref "U28") (pin "L2") (pinfunction "WE_n//A14_L2") (pintype "input"))
      (node (ref "U29") (pin "L2") (pinfunction "WE_n//A14_L2") (pintype "input"))
    )
    (net (code "72") (name "GND") (class "Default")
      (node (ref "C183") (pin "1") (pinfunction "1_1") (pintype "passive"))
      (node (ref "C184") (pin "1") (pinfunction "1_1") (pintype "passive"))
      (node (ref "C185") (pin "1") (pinfunction "1_1") (pintype "passive"))
      (node (ref "C186") (pin "1") (pinfunction "1_1") (pintype "passive"))
      (node (ref "C187") (pin "1") (pinfunction "1_1") (pintype "passive"))
      (node (ref "C188") (pin "1") (pinfunction "1_1") (pintype "passive"))
      (node (ref "C189") (pin "1") (pinfunction "1_1") (pintype "passive"))
      (node (ref "C198") (pin "1") (pinfunction "1_1") (pintype "passive"))
      (node (ref "C202") (pin "1") (pinfunction "1_1") (pintype "passive"))
      (node (ref "C211") (pin "1") (pinfunction "1_1") (pintype "passive"))
      (node (ref "C226") (pin "1") (pinfunction "1_1") (pintype "passive"))
      (node (ref "C236") (pin "1") (pinfunction "1_1") (pintype "passive"))
      (node (ref "C238") (pin "1") (pinfunction "1_1") (pintype "passive"))
      (node (ref "C239") (pin "1") (pinfunction "1_1") (pintype "passive"))
      (node (ref "C245") (pin "1") (pinfunction "1_1") (pintype "passive"))
      (node (ref "C247") (pin "1") (pinfunction "1_1") (pintype "passive"))
      (node (ref "C254") (pin "1") (pinfunction "1_1") (pintype "passive"))
      (node (ref "C255") (pin "1") (pinfunction "1_1") (pintype "passive"))
      (node (ref "C256") (pin "1") (pinfunction "1_1") (pintype "passive"))
      (node (ref "C257") (pin "1") (pinfunction "1_1") (pintype "passive"))
      (node (ref "C258") (pin "1") (pinfunction "1_1") (pintype "passive"))
      (node (ref "C259") (pin "1") (pinfunction "1_1") (pintype "passive"))
      (node (ref "C261") (pin "1") (pinfunction "1_1") (pintype "passive"))
      (node (ref "C262") (pin "1") (pinfunction "1_1") (pintype "passive"))
      (node (ref "C264") (pin "1") (pinfunction "1_1") (pintype "passive"))
      (node (ref "C48") (pin "1") (pinfunction "1_1") (pintype "passive"))
      (node (ref "C49") (pin "1") (pinfunction "1_1") (pintype "passive"))
      (node (ref "C50") (pin "1") (pinfunction "1_1") (pintype "passive"))
      (node (ref "C51") (pin "1") (pinfunction "1_1") (pintype "passive"))
      (node (ref "C77") (pin "1") (pinfunction "1_1") (pintype "passive"))
      (node (ref "C78") (pin "1") (pinfunction "1_1") (pintype "passive"))
      (node (ref "C79") (pin "1") (pinfunction "1_1") (pintype "passive"))
      (node (ref "C80") (pin "1") (pinfunction "1_1") (pintype "passive"))
      (node (ref "C82") (pin "1") (pinfunction "1_1") (pintype "passive"))
      (node (ref "C83") (pin "1") (pinfunction "1_1") (pintype "passive"))
      (node (ref "C84") (pin "1") (pinfunction "1_1") (pintype "passive"))
      (node (ref "C85") (pin "1") (pinfunction "1_1") (pintype "passive"))
      (node (ref "C93") (pin "1") (pinfunction "1_1") (pintype "passive"))
      (node (ref "C94") (pin "1") (pinfunction "1_1") (pintype "passive"))
      (node (ref "C95") (pin "1") (pinfunction "1_1") (pintype "passive"))
      (node (ref "C99") (pin "1") (pinfunction "1_1") (pintype "passive"))
      (node (ref "R252") (pin "1") (pinfunction "1_1") (pintype "passive"))
      (node (ref "R262") (pin "1") (pinfunction "1_1") (pintype "passive"))
      (node (ref "R63") (pin "1") (pinfunction "1_1") (pintype "passive"))
      (node (ref "R73") (pin "1") (pinfunction "1_1") (pintype "passive"))
      (node (ref "U28") (pin "A2") (pinfunction "VSSQ_A2") (pintype "power_in"))
      (node (ref "U28") (pin "A8") (pinfunction "VSSQ_A8") (pintype "power_in"))
      (node (ref "U28") (pin "B2") (pinfunction "VSS_B2") (pintype "power_in"))
      (node (ref "U28") (pin "C9") (pinfunction "VSSQ_C9") (pintype "power_in"))
      (node (ref "U28") (pin "D2") (pinfunction "VSSQ_D2") (pintype "power_in"))
      (node (ref "U28") (pin "D8") (pinfunction "VSSQ_D8") (pintype "power_in"))
      (node (ref "U28") (pin "E1") (pinfunction "VSS_E1") (pintype "power_in"))
      (node (ref "U28") (pin "E3") (pinfunction "VSSQ_E3") (pintype "power_in"))
      (node (ref "U28") (pin "E8") (pinfunction "VSSQ_E8") (pintype "power_in"))
      (node (ref "U28") (pin "E9") (pinfunction "VSS_E9") (pintype "power_in"))
      (node (ref "U28") (pin "F1") (pinfunction "VSSQ_F1") (pintype "power_in"))
      (node (ref "U28") (pin "G8") (pinfunction "VSS_G8") (pintype "power_in"))
      (node (ref "U28") (pin "H1") (pinfunction "VSSQ_H1") (pintype "power_in"))
      (node (ref "U28") (pin "H9") (pinfunction "VSSQ_H9") (pintype "power_in"))
      (node (ref "U28") (pin "K1") (pinfunction "VSS_K1") (pintype "power_in"))
      (node (ref "U28") (pin "K9") (pinfunction "VSS_K9") (pintype "power_in"))
      (node (ref "U28") (pin "M9") (pinfunction "VSS_M9") (pintype "power_in"))
      (node (ref "U28") (pin "N1") (pinfunction "VSS_N1") (pintype "power_in"))
      (node (ref "U28") (pin "N9") (pinfunction "TEN_N9") (pintype "input"))
      (node (ref "U28") (pin "T1") (pinfunction "VSS_T1") (pintype "power_in"))
      (node (ref "U28") (pin "T3") (pinfunction "PAR_T3") (pintype "input"))
      (node (ref "U29") (pin "A2") (pinfunction "VSSQ_A2") (pintype "power_in"))
      (node (ref "U29") (pin "A8") (pinfunction "VSSQ_A8") (pintype "power_in"))
      (node (ref "U29") (pin "B2") (pinfunction "VSS_B2") (pintype "power_in"))
      (node (ref "U29") (pin "C9") (pinfunction "VSSQ_C9") (pintype "power_in"))
      (node (ref "U29") (pin "D2") (pinfunction "VSSQ_D2") (pintype "power_in"))
      (node (ref "U29") (pin "D8") (pinfunction "VSSQ_D8") (pintype "power_in"))
      (node (ref "U29") (pin "E1") (pinfunction "VSS_E1") (pintype "power_in"))
      (node (ref "U29") (pin "E3") (pinfunction "VSSQ_E3") (pintype "power_in"))
      (node (ref "U29") (pin "E8") (pinfunction "VSSQ_E8") (pintype "power_in"))
      (node (ref "U29") (pin "E9") (pinfunction "VSS_E9") (pintype "power_in"))
      (node (ref "U29") (pin "F1") (pinfunction "VSSQ_F1") (pintype "power_in"))
      (node (ref "U29") (pin "G8") (pinfunction "VSS_G8") (pintype "power_in"))
      (node (ref "U29") (pin "H1") (pinfunction "VSSQ_H1") (pintype "power_in"))
      (node (ref "U29") (pin "H9") (pinfunction "VSSQ_H9") (pintype "power_in"))
      (node (ref "U29") (pin "K1") (pinfunction "VSS_K1") (pintype "power_in"))
      (node (ref "U29") (pin "K9") (pinfunction "VSS_K9") (pintype "power_in"))
      (node (ref "U29") (pin "M9") (pinfunction "VSS_M9") (pintype "power_in"))
      (node (ref "U29") (pin "N1") (pinfunction "VSS_N1") (pintype "power_in"))
      (node (ref "U29") (pin "N9") (pinfunction "TEN_N9") (pintype "input"))
      (node (ref "U29") (pin "T1") (pinfunction "VSS_T1") (pintype "power_in"))
      (node (ref "U29") (pin "T3") (pinfunction "PAR_T3") (pintype "input"))
    )
    (net (code "73") (name "Net-(U27F-DDR_VREF)") (class "Default")
      (node (ref "TP10") (pin "1") (pinfunction "1_1") (pintype "passive"))
      (node (ref "U27") (pin "L20") (pinfunction "DDR_VREF_L20") (pintype "passive"))
    )
    (net (code "74") (name "Net-(U27F-DDR_ZQ)") (class "Default")
      (node (ref "R262") (pin "2") (pinfunction "2_2") (pintype "passive"))
      (node (ref "U27") (pin "K16") (pinfunction "DDR_ZQ_K16") (pintype "passive"))
    )
    (net (code "75") (name "Net-(U28-ZQ)") (class "Default")
      (node (ref "R63") (pin "2") (pinfunction "2_2") (pintype "passive"))
      (node (ref "U28") (pin "F9") (pinfunction "ZQ_F9") (pintype "input"))
    )
    (net (code "76") (name "Net-(U29-ZQ)") (class "Default")
      (node (ref "R73") (pin "2") (pinfunction "2_2") (pintype "passive"))
      (node (ref "U29") (pin "F9") (pinfunction "ZQ_F9") (pintype "input"))
    )
    (net (code "77") (name "VDD_DDR") (class "Default")
      (node (ref "C188") (pin "2") (pinfunction "2_2") (pintype "passive"))
      (node (ref "C189") (pin "2") (pinfunction "2_2") (pintype "passive"))
      (node (ref "C202") (pin "2") (pinfunction "2_2") (pintype "passive"))
      (node (ref "C236") (pin "2") (pinfunction "2_2") (pintype "passive"))
      (node (ref "C238") (pin "2") (pinfunction "2_2") (pintype "passive"))
      (node (ref "C247") (pin "2") (pinfunction "2_2") (pintype "passive"))
      (node (ref "C261") (pin "2") (pinfunction "2_2") (pintype "passive"))
      (node (ref "C262") (pin "2") (pinfunction "2_2") (pintype "passive"))
      (node (ref "C264") (pin "2") (pinfunction "2_2") (pintype "passive"))
      (node (ref "C48") (pin "2") (pinfunction "2_2") (pintype "passive"))
      (node (ref "C50") (pin "2") (pinfunction "2_2") (pintype "passive"))
      (node (ref "C51") (pin "2") (pinfunction "2_2") (pintype "passive"))
      (node (ref "C77") (pin "2") (pinfunction "2_2") (pintype "passive"))
      (node (ref "C79") (pin "2") (pinfunction "2_2") (pintype "passive"))
      (node (ref "C80") (pin "2") (pinfunction "2_2") (pintype "passive"))
      (node (ref "C82") (pin "2") (pinfunction "2_2") (pintype "passive"))
      (node (ref "C84") (pin "2") (pinfunction "2_2") (pintype "passive"))
      (node (ref "C85") (pin "2") (pinfunction "2_2") (pintype "passive"))
      (node (ref "C93") (pin "2") (pinfunction "2_2") (pintype "passive"))
      (node (ref "C94") (pin "2") (pinfunction "2_2") (pintype "passive"))
      (node (ref "C99") (pin "2") (pinfunction "2_2") (pintype "passive"))
      (node (ref "U28") (pin "A1") (pinfunction "VDDQ_A1") (pintype "power_in"))
      (node (ref "U28") (pin "A9") (pinfunction "VDDQ_A9") (pintype "power_in"))
      (node (ref "U28") (pin "B3") (pinfunction "VDD_B3") (pintype "power_in"))
      (node (ref "U28") (pin "B9") (pinfunction "VDD_B9") (pintype "power_in"))
      (node (ref "U28") (pin "C1") (pinfunction "VDDQ_C1") (pintype "power_in"))
      (node (ref "U28") (pin "D1") (pinfunction "VDD_D1") (pintype "power_in"))
      (node (ref "U28") (pin "D9") (pinfunction "VDDQ_D9") (pintype "power_in"))
      (node (ref "U28") (pin "F2") (pinfunction "VDDQ_F2") (pintype "power_in"))
      (node (ref "U28") (pin "F8") (pinfunction "VDDQ_F8") (pintype "power_in"))
      (node (ref "U28") (pin "G1") (pinfunction "VDDQ_G1") (pintype "power_in"))
      (node (ref "U28") (pin "G7") (pinfunction "VDD_G7") (pintype "power_in"))
      (node (ref "U28") (pin "G9") (pinfunction "VDDQ_G9") (pintype "power_in"))
      (node (ref "U28") (pin "J1") (pinfunction "VDD_J1") (pintype "power_in"))
      (node (ref "U28") (pin "J2") (pinfunction "VDDQ_J2") (pintype "power_in"))
      (node (ref "U28") (pin "J8") (pinfunction "VDDQ_J8") (pintype "power_in"))
      (node (ref "U28") (pin "J9") (pinfunction "VDD_J9") (pintype "power_in"))
      (node (ref "U28") (pin "L1") (pinfunction "VDD_L1") (pintype "power_in"))
      (node (ref "U28") (pin "L9") (pinfunction "VDD_L9") (pintype "power_in"))
      (node (ref "U28") (pin "R1") (pinfunction "VDD_R1") (pintype "power_in"))
      (node (ref "U28") (pin "T9") (pinfunction "VDD_T9") (pintype "power_in"))
      (node (ref "U29") (pin "A1") (pinfunction "VDDQ_A1") (pintype "power_in"))
      (node (ref "U29") (pin "A9") (pinfunction "VDDQ_A9") (pintype "power_in"))
      (node (ref "U29") (pin "B3") (pinfunction "VDD_B3") (pintype "power_in"))
      (node (ref "U29") (pin "B9") (pinfunction "VDD_B9") (pintype "power_in"))
      (node (ref "U29") (pin "C1") (pinfunction "VDDQ_C1") (pintype "power_in"))
      (node (ref "U29") (pin "D1") (pinfunction "VDD_D1") (pintype "power_in"))
      (node (ref "U29") (pin "D9") (pinfunction "VDDQ_D9") (pintype "power_in"))
      (node (ref "U29") (pin "F2") (pinfunction "VDDQ_F2") (pintype "power_in"))
      (node (ref "U29") (pin "F8") (pinfunction "VDDQ_F8") (pintype "power_in"))
      (node (ref "U29") (pin "G1") (pinfunction "VDDQ_G1") (pintype "power_in"))
      (node (ref "U29") (pin "G7") (pinfunction "VDD_G7") (pintype "power_in"))
      (node (ref "U29") (pin "G9") (pinfunction "VDDQ_G9") (pintype "power_in"))
      (node (ref "U29") (pin "J1") (pinfunction "VDD_J1") (pintype "power_in"))
      (node (ref "U29") (pin "J2") (pinfunction "VDDQ_J2") (pintype "power_in"))
      (node (ref "U29") (pin "J8") (pinfunction "VDDQ_J8") (pintype "power_in"))
      (node (ref "U29") (pin "J9") (pinfunction "VDD_J9") (pintype "power_in"))
      (node (ref "U29") (pin "L1") (pinfunction "VDD_L1") (pintype "power_in"))
      (node (ref "U29") (pin "L9") (pinfunction "VDD_L9") (pintype "power_in"))
      (node (ref "U29") (pin "R1") (pinfunction "VDD_R1") (pintype "power_in"))
      (node (ref "U29") (pin "T9") (pinfunction "VDD_T9") (pintype "power_in"))
    )
    (net (code "78") (name "VPP_DDR") (class "Default")
      (node (ref "C198") (pin "2") (pinfunction "2_2") (pintype "passive"))
      (node (ref "C245") (pin "2") (pinfunction "2_2") (pintype "passive"))
      (node (ref "C83") (pin "2") (pinfunction "2_2") (pintype "passive"))
      (node (ref "C95") (pin "2") (pinfunction "2_2") (pintype "passive"))
      (node (ref "U28") (pin "B1") (pinfunction "VPP_B1") (pintype "power_in"))
      (node (ref "U28") (pin "R9") (pinfunction "VPP_R9") (pintype "power_in"))
      (node (ref "U29") (pin "B1") (pinfunction "VPP_B1") (pintype "power_in"))
      (node (ref "U29") (pin "R9") (pinfunction "VPP_R9") (pintype "power_in"))
    )
    (net (code "79") (name "VREF_DDR") (class "Default")
      (node (ref "C49") (pin "2") (pinfunction "2_2") (pintype "passive"))
      (node (ref "C78") (pin "2") (pinfunction "2_2") (pintype "passive"))
      (node (ref "U28") (pin "M1") (pinfunction "VREFCA_M1") (pintype "input"))
      (node (ref "U29") (pin "M1") (pinfunction "VREFCA_M1") (pintype "input"))
    )
    (net (code "80") (name "VTT_DDR") (class "Default")
      (node (ref "C183") (pin "2") (pinfunction "2_2") (pintype "passive"))
      (node (ref "C184") (pin "2") (pinfunction "2_2") (pintype "passive"))
      (node (ref "C185") (pin "2") (pinfunction "2_2") (pintype "passive"))
      (node (ref "C186") (pin "2") (pinfunction "2_2") (pintype "passive"))
      (node (ref "C187") (pin "2") (pinfunction "2_2") (pintype "passive"))
      (node (ref "C211") (pin "2") (pinfunction "2_2") (pintype "passive"))
      (node (ref "C226") (pin "2") (pinfunction "2_2") (pintype "passive"))
      (node (ref "C239") (pin "2") (pinfunction "2_2") (pintype "passive"))
      (node (ref "C254") (pin "2") (pinfunction "2_2") (pintype "passive"))
      (node (ref "C255") (pin "2") (pinfunction "2_2") (pintype "passive"))
      (node (ref "C256") (pin "2") (pinfunction "2_2") (pintype "passive"))
      (node (ref "C257") (pin "2") (pinfunction "2_2") (pintype "passive"))
      (node (ref "C258") (pin "2") (pinfunction "2_2") (pintype "passive"))
      (node (ref "C259") (pin "2") (pinfunction "2_2") (pintype "passive"))
      (node (ref "R253") (pin "2") (pinfunction "2_2") (pintype "passive"))
      (node (ref "R254") (pin "2") (pinfunction "2_2") (pintype "passive"))
      (node (ref "R255") (pin "2") (pinfunction "2_2") (pintype "passive"))
      (node (ref "R256") (pin "2") (pinfunction "2_2") (pintype "passive"))
      (node (ref "R257") (pin "2") (pinfunction "2_2") (pintype "passive"))
      (node (ref "R258") (pin "2") (pinfunction "2_2") (pintype "passive"))
      (node (ref "R259") (pin "2") (pinfunction "2_2") (pintype "passive"))
      (node (ref "R263") (pin "2") (pinfunction "2_2") (pintype "passive"))
      (node (ref "R264") (pin "2") (pinfunction "2_2") (pintype "passive"))
      (node (ref "R265") (pin "2") (pinfunction "2_2") (pintype "passive"))
      (node (ref "R266") (pin "2") (pinfunction "2_2") (pintype "passive"))
      (node (ref "R268") (pin "2") (pinfunction "2_2") (pintype "passive"))
      (node (ref "R271") (pin "2") (pinfunction "2_2") (pintype "passive"))
      (node (ref "R273") (pin "2") (pinfunction "2_2") (pintype "passive"))
      (node (ref "R275") (pin "2") (pinfunction "2_2") (pintype "passive"))
      (node (ref "R276") (pin "2") (pinfunction "2_2") (pintype "passive"))
      (node (ref "R277") (pin "2") (pinfunction "2_2") (pintype "passive"))
      (node (ref "R278") (pin "2") (pinfunction "2_2") (pintype "passive"))
      (node (ref "R279") (pin "2") (pinfunction "2_2") (pintype "passive"))
      (node (ref "R280") (pin "2") (pinfunction "2_2") (pintype "passive"))
      (node (ref "R281") (pin "2") (pinfunction "2_2") (pintype "passive"))
      (node (ref "R282") (pin "2") (pinfunction "2_2") (pintype "passive"))
      (node (ref "R283") (pin "2") (pinfunction "2_2") (pintype "passive"))
      (node (ref "R284") (pin "2") (pinfunction "2_2") (pintype "passive"))
    )
    (net (code "81") (name "unconnected-(U27F-DDR_A1-PadU18)") (class "Default")
      (node (ref "U27") (pin "U18") (pinfunction "DDR_A1_U18") (pintype "passive+no_connect"))
    )
    (net (code "82") (name "unconnected-(U27F-DDR_A6-PadT18)") (class "Default")
      (node (ref "U27") (pin "T18") (pinfunction "DDR_A6_T18") (pintype "passive+no_connect"))
    )
    (net (code "83") (name "unconnected-(U27F-DDR_A7-PadU19)") (class "Default")
      (node (ref "U27") (pin "U19") (pinfunction "DDR_A7_U19") (pintype "passive+no_connect"))
    )
    (net (code "84") (name "unconnected-(U27F-DDR_A16-PadJ18)") (class "Default")
      (node (ref "U27") (pin "J18") (pinfunction "DDR_A16_J18") (pintype "passive+no_connect"))
    )
    (net (code "85") (name "unconnected-(U27F-DDR_A19-PadK17)") (class "Default")
      (node (ref "U27") (pin "K17") (pinfunction "DDR_A19_K17") (pintype "passive+no_connect"))
    )
    (net (code "86") (name "unconnected-(U28-ALERT_n-PadP9)") (class "Default")
      (node (ref "U28") (pin "P9") (pinfunction "ALERT_n_P9") (pintype "output+no_connect"))
    )
    (net (code "87") (name "unconnected-(U28-NC-PadT7)") (class "Default")
      (node (ref "U28") (pin "T7") (pinfunction "NC_T7") (pintype "input+no_connect"))
    )
    (net (code "88") (name "unconnected-(U29-ALERT_n-PadP9)") (class "Default")
      (node (ref "U29") (pin "P9") (pinfunction "ALERT_n_P9") (pintype "output+no_connect"))
    )
    (net (code "89") (name "unconnected-(U29-NC-PadT7)") (class "Default")
      (node (ref "U29") (pin "T7") (pinfunction "NC_T7") (pintype "input+no_connect"))
    )
  )
)
